# MK12_PIR_LUX.net
KiCad netlist of a schematic drawn in EAGLE
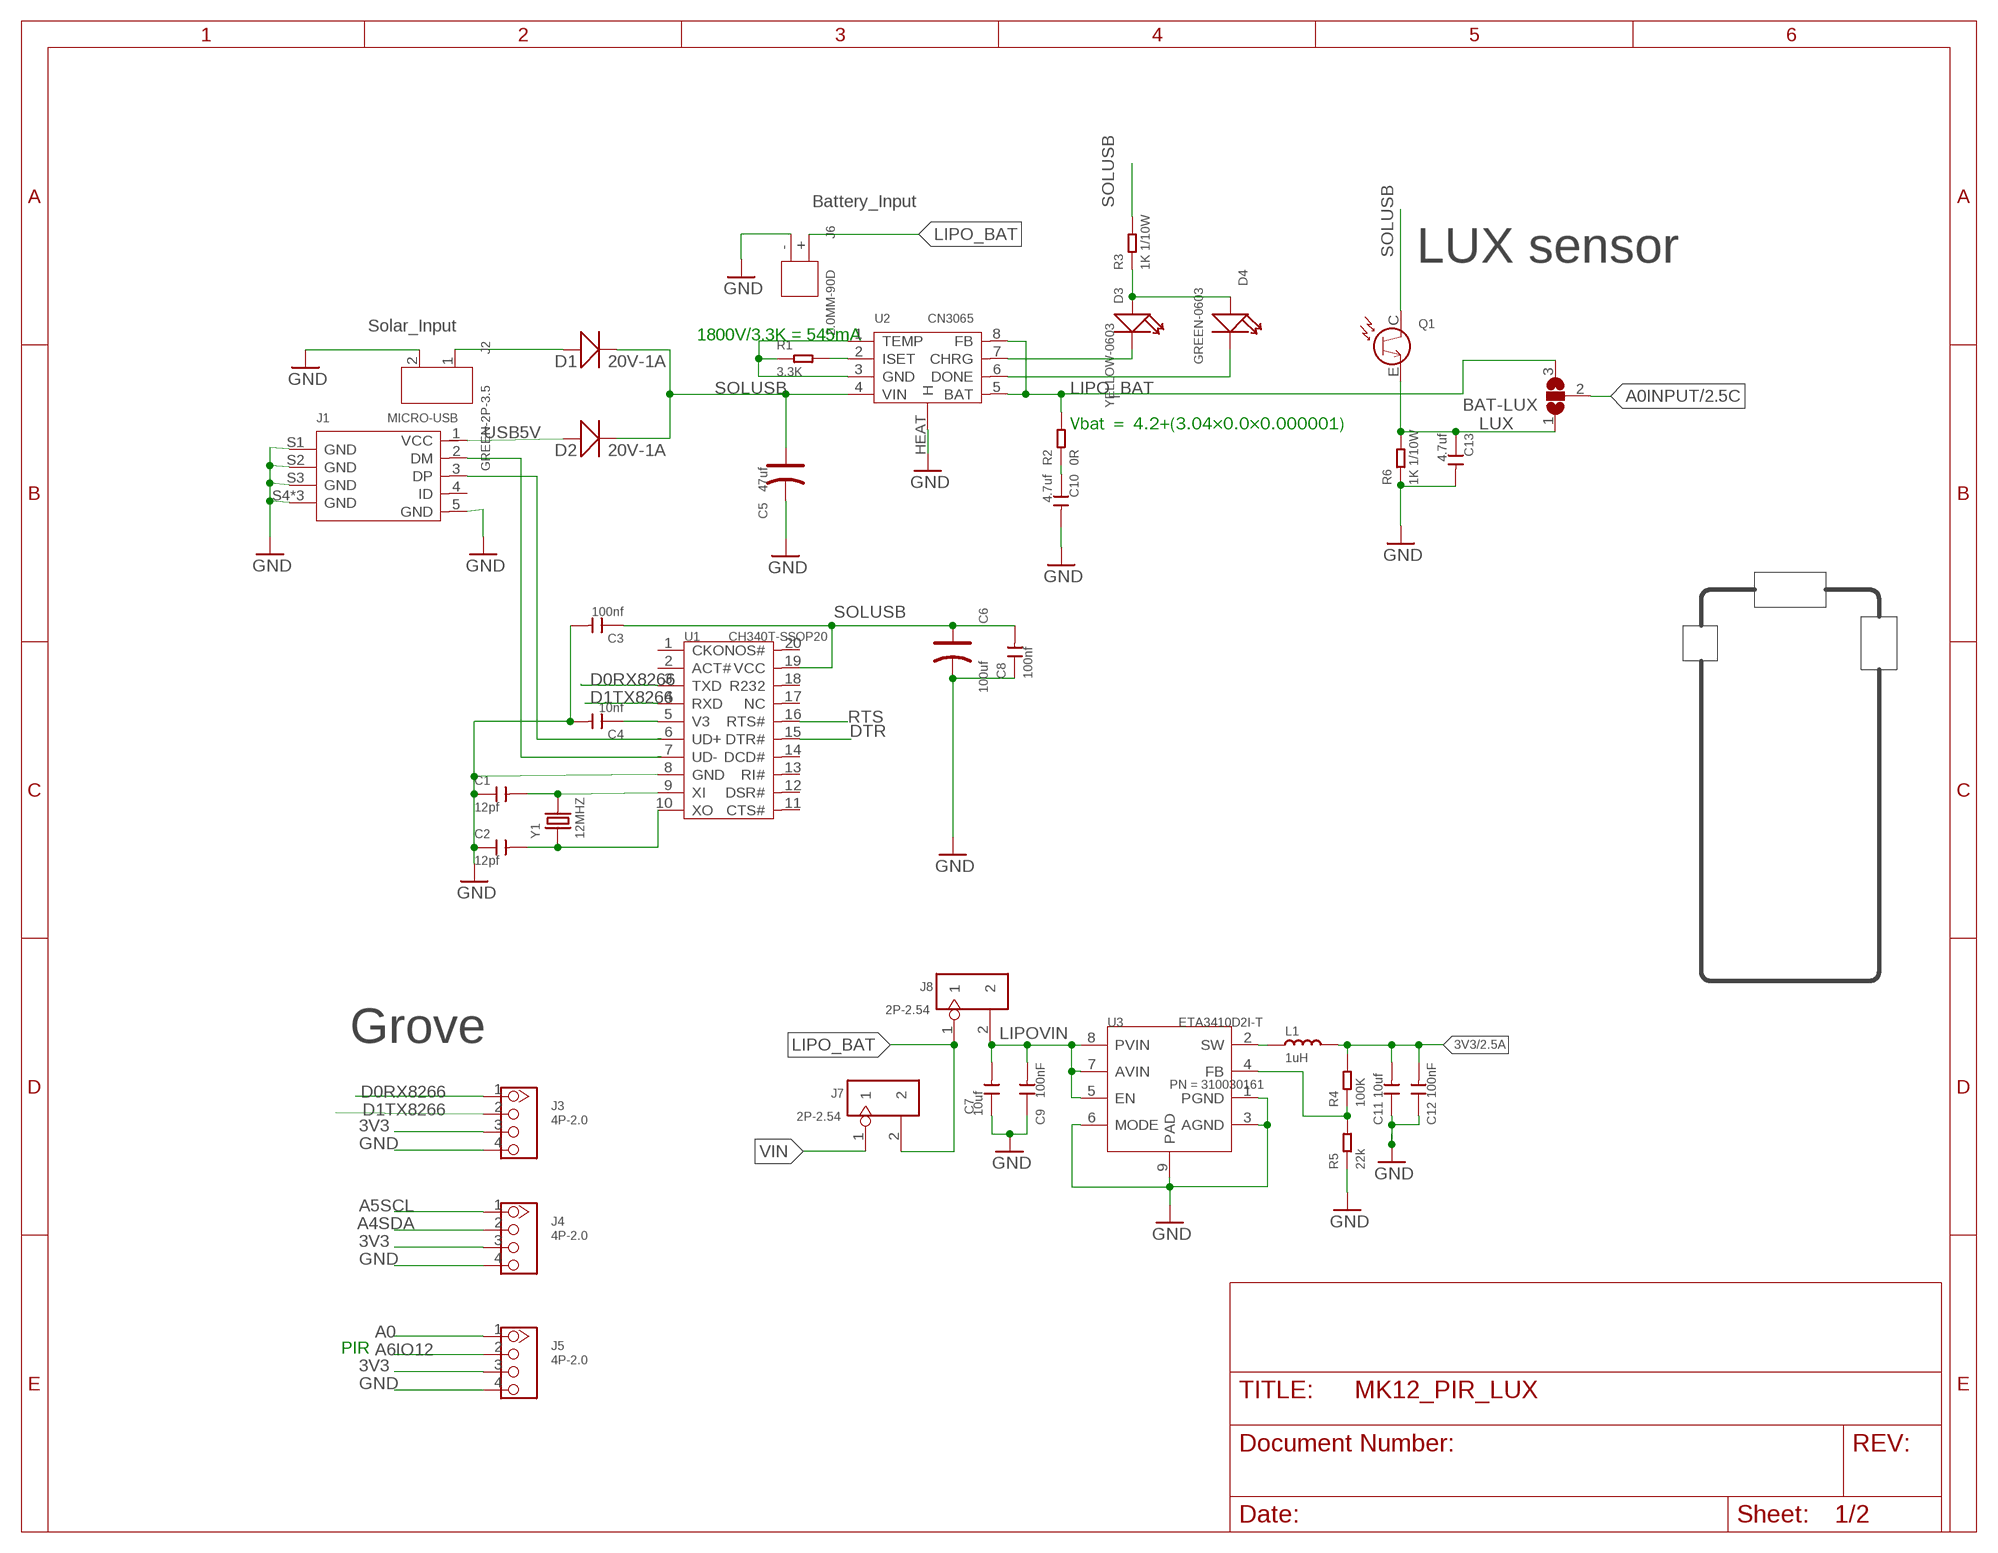
[diagram p0: schematic, sheet 1]
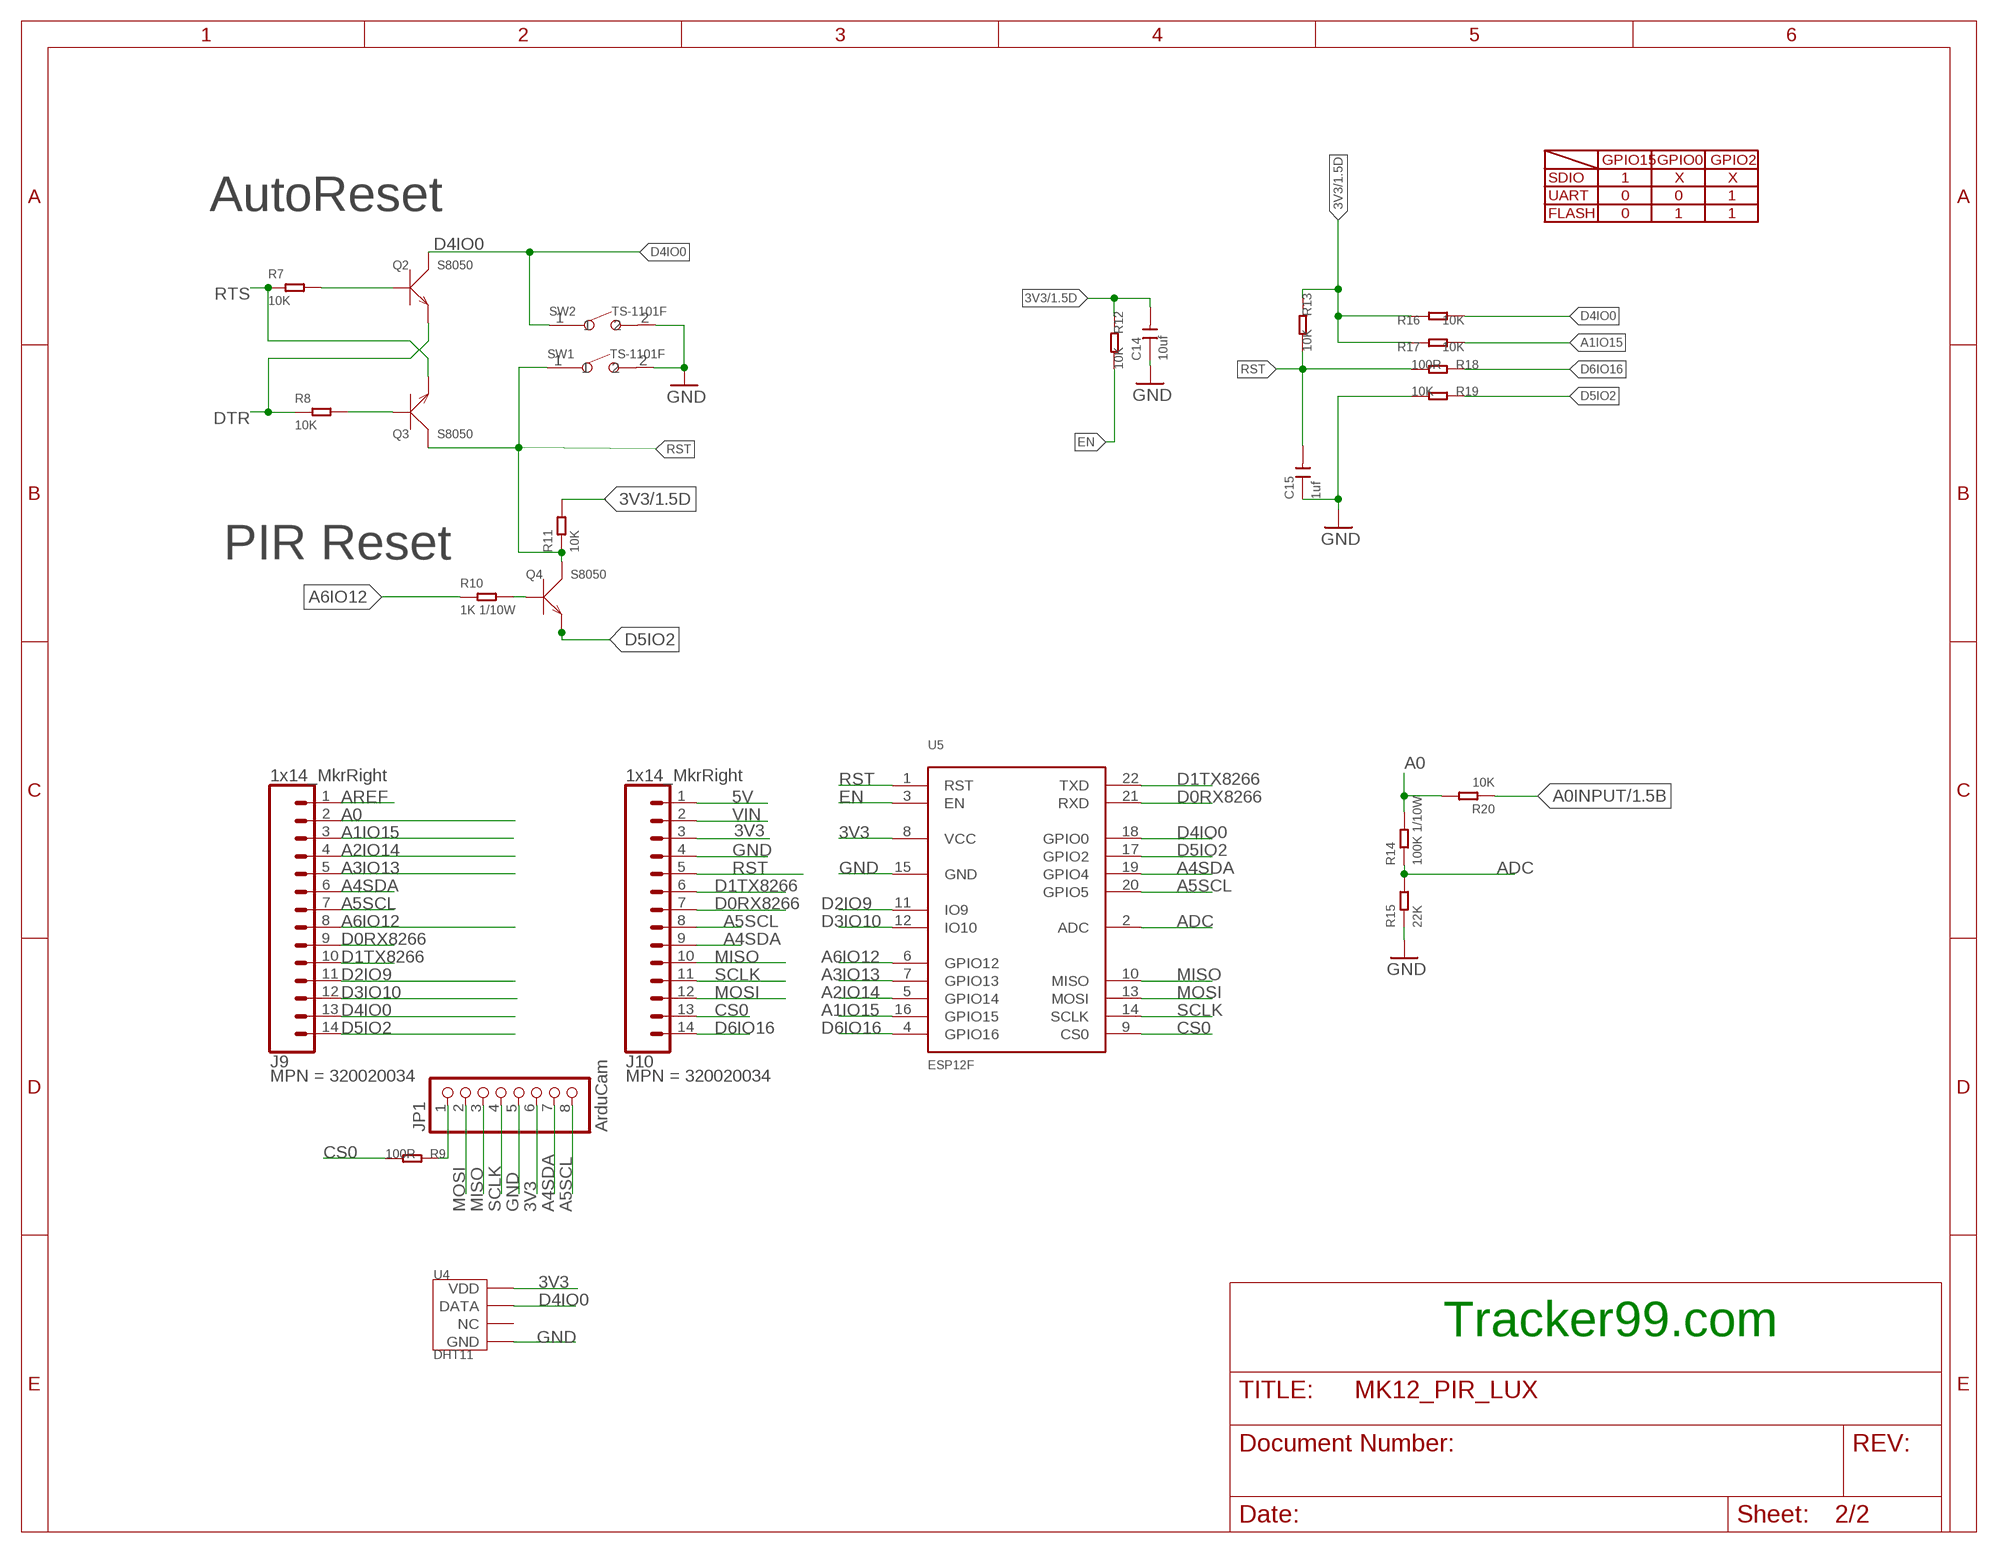
[diagram p1: schematic, sheet 2]

(export (version "E")
  (design (tool "Eeschema 10.0.6"))
  (components
    (comp (ref "BAT-LUX")
      (value "SJ2W")
      (footprint "eagle-import:SJ_2")
      (libsource (lib "eagle-import") (part "SJ2W"))
    )
    (comp (ref "C1")
      (value "12pf")
      (footprint "eagle-import:C0402")
      (fields (field (name "MPN") "CC0402JRNPO9BN120"))
      (libsource (lib "eagle-import") (part "CERAMIC-12PF-50V-5%-NPO(0402)"))
    )
    (comp (ref "C2")
      (value "12pf")
      (footprint "eagle-import:C0402")
      (fields (field (name "MPN") "CC0402JRNPO9BN120"))
      (libsource (lib "eagle-import") (part "CERAMIC-12PF-50V-5%-NPO(0402)"))
    )
    (comp (ref "C3")
      (value "100nf")
      (footprint "eagle-import:C0603")
      (fields (field (name "MPN") "CC0603KRX7R9BB104"))
      (libsource (lib "eagle-import") (part "CERAMIC-100NF-50V-10%-X7R(0603)"))
    )
    (comp (ref "C4")
      (value "10nf")
      (footprint "eagle-import:C0603")
      (fields (field (name "MPN") "CC0603KRX7R9BB103"))
      (libsource (lib "eagle-import") (part "CERAMIC-10NF-50V-10%-X7R(0603)"))
    )
    (comp (ref "C5")
      (value "47uf")
      (footprint "eagle-import:AVX-A")
      (fields (field (name "MPN") "TAJA476*006#NJ"))
      (libsource (lib "eagle-import") (part "TANTALUM-SMD-47UF-6.3V(AVX-A)"))
    )
    (comp (ref "C6")
      (value "100uf")
      (footprint "eagle-import:AVX-B")
      (fields (field (name "MPN") "TAJB107M010#NJ"))
      (libsource (lib "eagle-import") (part "TANTALUM-SMD-100UF-10V(AVX-B)"))
    )
    (comp (ref "C7")
      (value "10uf")
      (footprint "eagle-import:C0805")
      (fields (field (name "MPN") "CC0805KKX5R8BB106"))
      (libsource (lib "eagle-import") (part "CERAMIC-10UF-25V-10%-X5R(0805)"))
    )
    (comp (ref "C8")
      (value "100nf")
      (footprint "eagle-import:C0603")
      (fields (field (name "MPN") "CC0603KRX7R9BB104"))
      (libsource (lib "eagle-import") (part "CERAMIC-100NF-50V-10%-X7R(0603)"))
    )
    (comp (ref "C9")
      (value "100nF")
      (footprint "eagle-import:C0402")
      (libsource (lib "eagle-import") (part "CAP-0402"))
    )
    (comp (ref "C10")
      (value "4.7uf")
      (footprint "eagle-import:C0603")
      (fields (field (name "MPN") "CC0603KRX5R6BB475"))
      (libsource (lib "eagle-import") (part "CERAMIC-4.7UF-10V-10%-X5R(0603)"))
    )
    (comp (ref "C11")
      (value "10uf")
      (footprint "eagle-import:C0805")
      (fields (field (name "MPN") "CC0805KKX5R8BB106"))
      (libsource (lib "eagle-import") (part "CERAMIC-10UF-25V-10%-X5R(0805)"))
    )
    (comp (ref "C12")
      (value "100nF")
      (footprint "eagle-import:C0402")
      (libsource (lib "eagle-import") (part "CAP-0402"))
    )
    (comp (ref "C13")
      (value "4.7uf")
      (footprint "eagle-import:C0603")
      (fields (field (name "MPN") "CC0603KRX5R6BB475"))
      (libsource (lib "eagle-import") (part "CERAMIC-4.7UF-10V-10%-X5R(0603)"))
    )
    (comp (ref "D1")
      (value "20V-1A")
      (footprint "eagle-import:SOD-123")
      (fields (field (name "MPN") "B5819W"))
      (libsource (lib "eagle-import") (part "SMD-DIODE-SCHOTTKY-20V-1A(SOD-123)"))
    )
    (comp (ref "D2")
      (value "20V-1A")
      (footprint "eagle-import:SOD-123")
      (fields (field (name "MPN") "B5819W"))
      (libsource (lib "eagle-import") (part "SMD-DIODE-SCHOTTKY-20V-1A(SOD-123)"))
    )
    (comp (ref "D3")
      (value "YELLOW-0603")
      (footprint "eagle-import:LED-0603")
      (fields (field (name "MPN") "19-217-Y5C-AM1N1VY-3T"))
      (libsource (lib "eagle-import") (part "SMD-LED-CLEAR-YELLOW(0603)"))
    )
    (comp (ref "D4")
      (value "GREEN-0603")
      (footprint "eagle-import:LED-0603")
      (fields (field (name "MPN") "19-217-G7C-AN1P2-3T"))
      (libsource (lib "eagle-import") (part "SMD-LED-CLEAR-GREEN(0603)"))
    )
    (comp (ref "J1")
      (value "MICRO-USB")
      (footprint "eagle-import:MICRO-USB5+4P-SMD-0.65-B")
      (fields (field (name "EAGLEUP") "USB-MICROB;2.54mm"))
      (libsource (lib "eagle-import") (part "MICRO-USB5+4P'5+4P'"))
    )
    (comp (ref "J2")
      (value "GREEN-2P-3.5")
      (footprint "eagle-import:H2-3.5-7.0X7.0MM")
      (libsource (lib "eagle-import") (part "SCREW-TERMINAL-GREEN(2P-3.5)"))
    )
    (comp (ref "J3")
      (value "4P-2.0")
      (footprint "eagle-import:HW4-2.0")
      (libsource (lib "eagle-import") (part "GROVE-CONNECTOR-DIP(4P-2.0)"))
    )
    (comp (ref "J4")
      (value "4P-2.0")
      (footprint "eagle-import:HW4-2.0")
      (libsource (lib "eagle-import") (part "GROVE-CONNECTOR-DIP(4P-2.0)"))
    )
    (comp (ref "J5")
      (value "4P-2.0")
      (footprint "eagle-import:HW4-2.0")
      (libsource (lib "eagle-import") (part "GROVE-CONNECTOR-DIP(4P-2.0)"))
    )
    (comp (ref "J6")
      (value "2.0MM-90D")
      (footprint "eagle-import:H2-2.0-90D")
      (libsource (lib "eagle-import") (part "CONN-HEADER-PH-SIDE-(2P-2.0MM)'90D'"))
    )
    (comp (ref "J7")
      (value "2P-2.54")
      (footprint "eagle-import:H2-2.54")
      (fields (field (name "MPN") "P125-1102A0BS116A3"))
      (libsource (lib "eagle-import") (part "DIP-WHITE-MALE-HEADER-VERT(2P-2.54)"))
    )
    (comp (ref "J8")
      (value "2P-2.54")
      (footprint "eagle-import:H2-2.54")
      (fields (field (name "MPN") "P125-1102A0BS116A3"))
      (libsource (lib "eagle-import") (part "DIP-WHITE-MALE-HEADER-VERT(2P-2.54)"))
    )
    (comp (ref "L1")
      (value "1uH")
      (footprint "eagle-import:L0603")
      (libsource (lib "eagle-import") (part "INDUCTOR/FERRITE-BEAD'0603'"))
    )
    (comp (ref "Q1")
      (value "EAALST05RDMA0")
      (footprint "eagle-import:EAALST05RDMA0")
      (libsource (lib "eagle-import") (part "EAALST05RDMA0"))
    )
    (comp (ref "R1")
      (value "3.3K")
      (footprint "eagle-import:R0603")
      (libsource (lib "eagle-import") (part "SMD-RES-3.3K-5%-1/10W(0603)"))
    )
    (comp (ref "R2")
      (value "0R")
      (footprint "eagle-import:R0603")
      (fields (field (name "MPN") "RC0603JR-070RL"))
      (libsource (lib "eagle-import") (part "SMD-RES-0R-5%-1/10W(0603)"))
    )
    (comp (ref "R3")
      (value "1K 1/10W")
      (footprint "eagle-import:R0603")
      (fields (field (name "MPN") "RC0603JR-071KL"))
      (libsource (lib "eagle-import") (part "SMD-RES-1K-5%-1/10W(0603)"))
    )
    (comp (ref "R4")
      (value "100K")
      (footprint "eagle-import:R0402")
      (fields (field (name "MPN") "RC0402FR-07100KL"))
      (libsource (lib "eagle-import") (part "SMD-RES-100K-1%-1/16W(0402)"))
    )
    (comp (ref "R5")
      (value "22k")
      (footprint "eagle-import:R0402")
      (fields (field (name "MPN") "RC0402FR-0722KL"))
      (libsource (lib "eagle-import") (part "SMD-RES-22K-1%-1/16W(0402)"))
    )
    (comp (ref "R6")
      (value "1K 1/10W")
      (footprint "eagle-import:R0603")
      (fields (field (name "MPN") "RC0603JR-071KL"))
      (libsource (lib "eagle-import") (part "SMD-RES-1K-5%-1/10W(0603)"))
    )
    (comp (ref "U1")
      (value "CH340T-SSOP20")
      (footprint "eagle-import:SSOP20-0.65-7.6X5.2MM")
      (fields (field (name "MPN") "CH340T"))
      (libsource (lib "eagle-import") (part "INTERFACE-CH340T(SSOP20)"))
    )
    (comp (ref "U2")
      (value "CN3065")
      (footprint "eagle-import:DFN-8")
      (libsource (lib "eagle-import") (part "PMIC-CN3065-DFN8"))
    )
    (comp (ref "U3")
      (value "ETA3410D2I-T")
      (footprint "eagle-import:DFN8G-0.5-2X2MM")
      (fields (field (name "PN") "310030161"))
      (libsource (lib "eagle-import") (part "CONVERTER-ETA3410"))
    )
    (comp (ref "Y1")
      (value "12MHZ")
      (footprint "eagle-import:X2-SMD-5.0X3.2X1.3MM")
      (fields (field (name "MPN") "5032/2P"))
      (libsource (lib "eagle-import") (part "SMD-CRYSTAL-12MHZ-20PF-20PPM-40R(2P-5.0X3.2MM)"))
    )
    (comp (ref "C14")
      (value "10uf")
      (footprint "eagle-import:C0603")
      (fields (field (name "MPN") "CC0603KRX5R6BB106"))
      (libsource (lib "eagle-import") (part "CERAMIC-10UF-10V-10%-X5R(0603)"))
    )
    (comp (ref "C15")
      (value "1uf")
      (footprint "eagle-import:C0603")
      (fields (field (name "MPN") "CC0603KRX7R8BB105"))
      (libsource (lib "eagle-import") (part "CERAMIC-1UF-25V-10%-X7R(0603)"))
    )
    (comp (ref "J9")
      (value "1x14_MkrRight")
      (footprint "eagle-import:1X14_LOCK")
      (fields (field (name "MPN") "320020034"))
      (libsource (lib "eagle-import") (part "CONN_14LOCK"))
    )
    (comp (ref "J10")
      (value "1x14_MkrRight")
      (footprint "eagle-import:1X14_LOCK")
      (fields (field (name "MPN") "320020034"))
      (libsource (lib "eagle-import") (part "CONN_14LOCK"))
    )
    (comp (ref "JP1")
      (value "ArduCam")
      (footprint "eagle-import:MILLER_1X08-LOCK")
      (libsource (lib "eagle-import") (part "MILLER_PINHD-1X8LOCK"))
    )
    (comp (ref "Q2")
      (value "S8050")
      (footprint "eagle-import:SOT-23")
      (libsource (lib "eagle-import") (part "SMD-TRANSISTORS-NPN-25V-500MW-S8050(SOT-23)"))
    )
    (comp (ref "Q3")
      (value "S8050")
      (footprint "eagle-import:SOT-23")
      (libsource (lib "eagle-import") (part "SMD-TRANSISTORS-NPN-25V-500MW-S8050(SOT-23)"))
    )
    (comp (ref "Q4")
      (value "S8050")
      (footprint "eagle-import:SOT-23")
      (libsource (lib "eagle-import") (part "SMD-TRANSISTORS-NPN-25V-500MW-S8050(SOT-23)"))
    )
    (comp (ref "R7")
      (value "10K")
      (footprint "eagle-import:R0402")
      (fields (field (name "MPN") "RC0402JR-0710KL"))
      (libsource (lib "eagle-import") (part "SMD-RES-10K-5%-1/(0402)"))
    )
    (comp (ref "R8")
      (value "10K")
      (footprint "eagle-import:R0402")
      (fields (field (name "MPN") "RC0402JR-0710KL"))
      (libsource (lib "eagle-import") (part "SMD-RES-10K-5%-1/(0402)"))
    )
    (comp (ref "R9")
      (value "100R")
      (footprint "eagle-import:R0603")
      (fields (field (name "MPN") "RC0603JR-07100RL"))
      (libsource (lib "eagle-import") (part "SMD-RES-100R-5%-1/10W(0603)"))
    )
    (comp (ref "R10")
      (value "1K 1/10W")
      (footprint "eagle-import:R0603")
      (fields (field (name "MPN") "RC0603JR-071KL"))
      (libsource (lib "eagle-import") (part "SMD-RES-1K-5%-1/10W(0603)"))
    )
    (comp (ref "R11")
      (value "10K")
      (footprint "eagle-import:R0402")
      (fields (field (name "MPN") "RC0402JR-0710KL"))
      (libsource (lib "eagle-import") (part "SMD-RES-10K-5%-1/(0402)"))
    )
    (comp (ref "R12")
      (value "10K")
      (footprint "eagle-import:SEEED-RESISTOR_R0402")
      (fields (field (name "MPN") "RC0402JR-0710KL"))
      (libsource (lib "eagle-import") (part "SEEED-RESISTOR_SMD-RES-10K-5%-1/(0402)"))
    )
    (comp (ref "R13")
      (value "10K")
      (footprint "eagle-import:SEEED-RESISTOR_R0402")
      (fields (field (name "MPN") "RC0402JR-0710KL"))
      (libsource (lib "eagle-import") (part "SEEED-RESISTOR_SMD-RES-10K-5%-1/(0402)"))
    )
    (comp (ref "R14")
      (value "100K 1/10W")
      (footprint "eagle-import:R0603")
      (fields (field (name "MPN") "RC0603JR-07100KL"))
      (libsource (lib "eagle-import") (part "SMD-RES-100K-5%-1/10W(0603)"))
    )
    (comp (ref "R15")
      (value "22K")
      (footprint "eagle-import:R0603")
      (fields (field (name "MPN") "RC0603JR-0722KL"))
      (libsource (lib "eagle-import") (part "SMD-RES-22K-5%-1/10W(0603)"))
    )
    (comp (ref "R16")
      (value "10K")
      (footprint "eagle-import:SEEED-RESISTOR_R0402")
      (fields (field (name "MPN") "RC0402JR-0710KL"))
      (libsource (lib "eagle-import") (part "SEEED-RESISTOR_SMD-RES-10K-5%-1/(0402)"))
    )
    (comp (ref "R17")
      (value "10K")
      (footprint "eagle-import:SEEED-RESISTOR_R0402")
      (fields (field (name "MPN") "RC0402JR-0710KL"))
      (libsource (lib "eagle-import") (part "SEEED-RESISTOR_SMD-RES-10K-5%-1/(0402)"))
    )
    (comp (ref "R18")
      (value "100R")
      (footprint "eagle-import:R0603")
      (fields (field (name "MPN") "RC0603JR-07100RL"))
      (libsource (lib "eagle-import") (part "SMD-RES-100R-5%-1/10W(0603)"))
    )
    (comp (ref "R19")
      (value "10K")
      (footprint "eagle-import:SEEED-RESISTOR_R0402")
      (fields (field (name "MPN") "RC0402JR-0710KL"))
      (libsource (lib "eagle-import") (part "SEEED-RESISTOR_SMD-RES-10K-5%-1/(0402)"))
    )
    (comp (ref "R20")
      (value "10K")
      (footprint "eagle-import:R0402")
      (fields (field (name "MPN") "RC0402JR-0710KL"))
      (libsource (lib "eagle-import") (part "SMD-RES-10K-5%-1/(0402)"))
    )
    (comp (ref "SW1")
      (value "TS-1101F")
      (footprint "eagle-import:SW2-5.0-6.0X3.0X4.3MM")
      (libsource (lib "eagle-import") (part "DIP-BUTTON(2P-6.0X3.0X4.3MM)-TS-1101F"))
    )
    (comp (ref "SW2")
      (value "TS-1101F")
      (footprint "eagle-import:SW2-5.0-6.0X3.0X4.3MM")
      (libsource (lib "eagle-import") (part "DIP-BUTTON(2P-6.0X3.0X4.3MM)-TS-1101F"))
    )
    (comp (ref "U4")
      (value "DHT11")
      (footprint "eagle-import:SNR4-2.54-15.5X12.0X5.5MM")
      (libsource (lib "eagle-import") (part "TEM-HUM-DHT11(4P-15.5X12.0MM)"))
    )
    (comp (ref "U5")
      (value "ESP12F")
      (footprint "eagle-import:ESP-12F")
      (libsource (lib "eagle-import") (part "ESP-12F"))
    )
  )
  (nets
    (net (code "1") (name "3V3") (class "Default")
      (node (ref "C11") (pin "2") (pinfunction "2_2") (pintype "passive"))
      (node (ref "C12") (pin "2") (pinfunction "2_2") (pintype "passive"))
      (node (ref "C14") (pin "2") (pinfunction "2_2") (pintype "passive"))
      (node (ref "J10") (pin "3") (pinfunction "3_3") (pintype "passive"))
      (node (ref "J3") (pin "3") (pinfunction "3_3") (pintype "bidirectional"))
      (node (ref "J4") (pin "3") (pinfunction "3_3") (pintype "bidirectional"))
      (node (ref "J5") (pin "3") (pinfunction "3_3") (pintype "bidirectional"))
      (node (ref "JP1") (pin "6") (pinfunction "6_6") (pintype "passive"))
      (node (ref "L1") (pin "2") (pinfunction "2_2") (pintype "passive"))
      (node (ref "R11") (pin "2") (pinfunction "2_2") (pintype "passive"))
      (node (ref "R12") (pin "1") (pinfunction "1_1") (pintype "passive"))
      (node (ref "R13") (pin "1") (pinfunction "1_1") (pintype "passive"))
      (node (ref "R16") (pin "1") (pinfunction "1_1") (pintype "passive"))
      (node (ref "R17") (pin "1") (pinfunction "1_1") (pintype "passive"))
      (node (ref "R4") (pin "2") (pinfunction "2_2") (pintype "passive"))
      (node (ref "U4") (pin "1") (pinfunction "VDD_1") (pintype "power_in"))
      (node (ref "U5") (pin "8") (pinfunction "VCC_8") (pintype "bidirectional"))
    )
    (net (code "2") (name "5V") (class "Default")
      (node (ref "J10") (pin "1") (pinfunction "1_1") (pintype "passive"))
    )
    (net (code "3") (name "A0") (class "Default")
      (node (ref "J5") (pin "1") (pinfunction "1_1") (pintype "bidirectional"))
      (node (ref "J9") (pin "2") (pinfunction "2_2") (pintype "passive"))
      (node (ref "R14") (pin "2") (pinfunction "2_2") (pintype "passive"))
      (node (ref "R20") (pin "2") (pinfunction "2_2") (pintype "passive"))
    )
    (net (code "4") (name "A0INPUT") (class "Default")
      (node (ref "BAT-LUX") (pin "2") (pinfunction "2_2") (pintype "passive"))
      (node (ref "R20") (pin "1") (pinfunction "1_1") (pintype "passive"))
    )
    (net (code "5") (name "A1IO15") (class "Default")
      (node (ref "J9") (pin "3") (pinfunction "3_3") (pintype "passive"))
      (node (ref "R17") (pin "2") (pinfunction "2_2") (pintype "passive"))
      (node (ref "U5") (pin "16") (pinfunction "GPIO15_16") (pintype "bidirectional"))
    )
    (net (code "6") (name "A2IO14") (class "Default")
      (node (ref "J9") (pin "4") (pinfunction "4_4") (pintype "passive"))
      (node (ref "U5") (pin "5") (pinfunction "GPIO14_5") (pintype "bidirectional"))
    )
    (net (code "7") (name "A3IO13") (class "Default")
      (node (ref "J9") (pin "5") (pinfunction "5_5") (pintype "passive"))
      (node (ref "U5") (pin "7") (pinfunction "GPIO13_7") (pintype "bidirectional"))
    )
    (net (code "8") (name "A4SDA") (class "Default")
      (node (ref "J10") (pin "9") (pinfunction "9_9") (pintype "passive"))
      (node (ref "J4") (pin "2") (pinfunction "2_2") (pintype "bidirectional"))
      (node (ref "J9") (pin "6") (pinfunction "6_6") (pintype "passive"))
      (node (ref "JP1") (pin "7") (pinfunction "7_7") (pintype "passive"))
      (node (ref "U5") (pin "19") (pinfunction "GPIO4_19") (pintype "bidirectional"))
    )
    (net (code "9") (name "A5SCL") (class "Default")
      (node (ref "J10") (pin "8") (pinfunction "8_8") (pintype "passive"))
      (node (ref "J4") (pin "1") (pinfunction "1_1") (pintype "bidirectional"))
      (node (ref "J9") (pin "7") (pinfunction "7_7") (pintype "passive"))
      (node (ref "JP1") (pin "8") (pinfunction "8_8") (pintype "passive"))
      (node (ref "U5") (pin "20") (pinfunction "GPIO5_20") (pintype "bidirectional"))
    )
    (net (code "10") (name "A6IO12") (class "Default")
      (node (ref "J5") (pin "2") (pinfunction "2_2") (pintype "bidirectional"))
      (node (ref "J9") (pin "8") (pinfunction "8_8") (pintype "passive"))
      (node (ref "R10") (pin "1") (pinfunction "1_1") (pintype "passive"))
      (node (ref "U5") (pin "6") (pinfunction "GPIO12_6") (pintype "bidirectional"))
    )
    (net (code "11") (name "ADC") (class "Default")
      (node (ref "R14") (pin "1") (pinfunction "1_1") (pintype "passive"))
      (node (ref "R15") (pin "2") (pinfunction "2_2") (pintype "passive"))
      (node (ref "U5") (pin "2") (pinfunction "ADC_2") (pintype "bidirectional"))
    )
    (net (code "12") (name "AREF") (class "Default")
      (node (ref "J9") (pin "1") (pinfunction "1_1") (pintype "passive"))
    )
    (net (code "13") (name "CS0") (class "Default")
      (node (ref "J10") (pin "13") (pinfunction "13_13") (pintype "passive"))
      (node (ref "R9") (pin "2") (pinfunction "2_2") (pintype "passive"))
      (node (ref "U5") (pin "9") (pinfunction "CS0_9") (pintype "bidirectional"))
    )
    (net (code "14") (name "D0RX8266") (class "Default")
      (node (ref "J10") (pin "7") (pinfunction "7_7") (pintype "passive"))
      (node (ref "J3") (pin "1") (pinfunction "1_1") (pintype "bidirectional"))
      (node (ref "J9") (pin "9") (pinfunction "9_9") (pintype "passive"))
      (node (ref "U1") (pin "3") (pinfunction "TXD_3") (pintype "output"))
      (node (ref "U5") (pin "21") (pinfunction "RXD_21") (pintype "bidirectional"))
    )
    (net (code "15") (name "D1TX8266") (class "Default")
      (node (ref "J10") (pin "6") (pinfunction "6_6") (pintype "passive"))
      (node (ref "J3") (pin "2") (pinfunction "2_2") (pintype "bidirectional"))
      (node (ref "J9") (pin "10") (pinfunction "10_10") (pintype "passive"))
      (node (ref "U1") (pin "4") (pinfunction "RXD_4") (pintype "input"))
      (node (ref "U5") (pin "22") (pinfunction "TXD_22") (pintype "bidirectional"))
    )
    (net (code "16") (name "D2IO9") (class "Default")
      (node (ref "J9") (pin "11") (pinfunction "11_11") (pintype "passive"))
      (node (ref "U5") (pin "11") (pinfunction "IO9_11") (pintype "bidirectional"))
    )
    (net (code "17") (name "D3IO10") (class "Default")
      (node (ref "J9") (pin "12") (pinfunction "12_12") (pintype "passive"))
      (node (ref "U5") (pin "12") (pinfunction "IO10_12") (pintype "bidirectional"))
    )
    (net (code "18") (name "D4IO0") (class "Default")
      (node (ref "J9") (pin "13") (pinfunction "13_13") (pintype "passive"))
      (node (ref "Q2") (pin "3") (pinfunction "C_3") (pintype "passive"))
      (node (ref "R16") (pin "2") (pinfunction "2_2") (pintype "passive"))
      (node (ref "SW2") (pin "1") (pinfunction "1_1") (pintype "bidirectional"))
      (node (ref "U4") (pin "2") (pinfunction "DATA_2") (pintype "bidirectional"))
      (node (ref "U5") (pin "18") (pinfunction "GPIO0_18") (pintype "bidirectional"))
    )
    (net (code "19") (name "D5IO2") (class "Default")
      (node (ref "J9") (pin "14") (pinfunction "14_14") (pintype "passive"))
      (node (ref "Q4") (pin "2") (pinfunction "E_2") (pintype "passive"))
      (node (ref "R19") (pin "1") (pinfunction "1_1") (pintype "passive"))
      (node (ref "U5") (pin "17") (pinfunction "GPIO2_17") (pintype "bidirectional"))
    )
    (net (code "20") (name "D6IO16") (class "Default")
      (node (ref "J10") (pin "14") (pinfunction "14_14") (pintype "passive"))
      (node (ref "R18") (pin "1") (pinfunction "1_1") (pintype "passive"))
      (node (ref "U5") (pin "4") (pinfunction "GPIO16_4") (pintype "bidirectional"))
    )
    (net (code "21") (name "DTR") (class "Default")
      (node (ref "Q2") (pin "2") (pinfunction "E_2") (pintype "passive"))
      (node (ref "R8") (pin "1") (pinfunction "1_1") (pintype "passive"))
      (node (ref "U1") (pin "15") (pinfunction "DTR#_15") (pintype "output"))
    )
    (net (code "22") (name "EN") (class "Default")
      (node (ref "R12") (pin "2") (pinfunction "2_2") (pintype "passive"))
      (node (ref "U5") (pin "3") (pinfunction "EN_3") (pintype "bidirectional"))
    )
    (net (code "23") (name "GND") (class "Default")
      (node (ref "C1") (pin "1") (pinfunction "1_1") (pintype "passive"))
      (node (ref "C10") (pin "2") (pinfunction "2_2") (pintype "passive"))
      (node (ref "C11") (pin "1") (pinfunction "1_1") (pintype "passive"))
      (node (ref "C12") (pin "1") (pinfunction "1_1") (pintype "passive"))
      (node (ref "C13") (pin "2") (pinfunction "2_2") (pintype "passive"))
      (node (ref "C14") (pin "1") (pinfunction "1_1") (pintype "passive"))
      (node (ref "C15") (pin "1") (pinfunction "1_1") (pintype "passive"))
      (node (ref "C2") (pin "1") (pinfunction "1_1") (pintype "passive"))
      (node (ref "C3") (pin "2") (pinfunction "2_2") (pintype "passive"))
      (node (ref "C4") (pin "2") (pinfunction "2_2") (pintype "passive"))
      (node (ref "C5") (pin "-") (pinfunction "-_-") (pintype "passive"))
      (node (ref "C6") (pin "-") (pinfunction "-_-") (pintype "passive"))
      (node (ref "C7") (pin "1") (pinfunction "1_1") (pintype "passive"))
      (node (ref "C8") (pin "1") (pinfunction "1_1") (pintype "passive"))
      (node (ref "C9") (pin "1") (pinfunction "1_1") (pintype "passive"))
      (node (ref "J1") (pin "5") (pinfunction "GND_5") (pintype "bidirectional"))
      (node (ref "J1") (pin "S1") (pinfunction "GND_S1") (pintype "bidirectional"))
      (node (ref "J1") (pin "S2") (pinfunction "GND_S2") (pintype "bidirectional"))
      (node (ref "J1") (pin "S3") (pinfunction "GND_S3") (pintype "bidirectional"))
      (node (ref "J1") (pin "S4") (pinfunction "GND_S4") (pintype "bidirectional"))
      (node (ref "J1") (pin "S5") (pinfunction "GND_S5") (pintype "bidirectional"))
      (node (ref "J1") (pin "S6") (pinfunction "GND_S6") (pintype "bidirectional"))
      (node (ref "J10") (pin "4") (pinfunction "4_4") (pintype "passive"))
      (node (ref "J2") (pin "2") (pinfunction "2_2") (pintype "bidirectional"))
      (node (ref "J3") (pin "4") (pinfunction "4_4") (pintype "bidirectional"))
      (node (ref "J4") (pin "4") (pinfunction "4_4") (pintype "bidirectional"))
      (node (ref "J5") (pin "4") (pinfunction "4_4") (pintype "bidirectional"))
      (node (ref "J6") (pin "-") (pinfunction "P$2_-") (pintype "bidirectional"))
      (node (ref "JP1") (pin "5") (pinfunction "5_5") (pintype "passive"))
      (node (ref "R1") (pin "1") (pinfunction "1_1") (pintype "passive"))
      (node (ref "R15") (pin "1") (pinfunction "1_1") (pintype "passive"))
      (node (ref "R19") (pin "2") (pinfunction "2_2") (pintype "passive"))
      (node (ref "R5") (pin "1") (pinfunction "1_1") (pintype "passive"))
      (node (ref "R6") (pin "1") (pinfunction "1_1") (pintype "passive"))
      (node (ref "SW1") (pin "2") (pinfunction "2_2") (pintype "bidirectional"))
      (node (ref "SW2") (pin "2") (pinfunction "2_2") (pintype "bidirectional"))
      (node (ref "U1") (pin "8") (pinfunction "GND_8") (pintype "power_in"))
      (node (ref "U2") (pin "1") (pinfunction "TEMP_1") (pintype "input"))
      (node (ref "U2") (pin "3") (pinfunction "GND_3") (pintype "power_in"))
      (node (ref "U2") (pin "HEAT") (pinfunction "H_HEAT") (pintype "bidirectional"))
      (node (ref "U3") (pin "1") (pinfunction "PGND_1") (pintype "bidirectional"))
      (node (ref "U3") (pin "3") (pinfunction "AGND_3") (pintype "bidirectional"))
      (node (ref "U3") (pin "6") (pinfunction "MODE_6") (pintype "bidirectional"))
      (node (ref "U3") (pin "9") (pinfunction "PAD_9") (pintype "bidirectional"))
      (node (ref "U4") (pin "4") (pinfunction "GND_4") (pintype "power_in"))
      (node (ref "U5") (pin "15") (pinfunction "GND_15") (pintype "bidirectional"))
    )
    (net (code "24") (name "LIPOVIN") (class "Default")
      (node (ref "C7") (pin "2") (pinfunction "2_2") (pintype "passive"))
      (node (ref "C9") (pin "2") (pinfunction "2_2") (pintype "passive"))
      (node (ref "J8") (pin "2") (pinfunction "2_2") (pintype "bidirectional"))
      (node (ref "U3") (pin "5") (pinfunction "EN_5") (pintype "bidirectional"))
      (node (ref "U3") (pin "7") (pinfunction "AVIN_7") (pintype "bidirectional"))
      (node (ref "U3") (pin "8") (pinfunction "PVIN_8") (pintype "bidirectional"))
    )
    (net (code "25") (name "LIPO_BAT") (class "Default")
      (node (ref "BAT-LUX") (pin "3") (pinfunction "3_3") (pintype "passive"))
      (node (ref "J6") (pin "+") (pinfunction "P$1_+") (pintype "bidirectional"))
      (node (ref "J7") (pin "2") (pinfunction "2_2") (pintype "bidirectional"))
      (node (ref "J8") (pin "1") (pinfunction "1_1") (pintype "bidirectional"))
      (node (ref "R2") (pin "2") (pinfunction "2_2") (pintype "passive"))
      (node (ref "U2") (pin "5") (pinfunction "BAT_5") (pintype "bidirectional"))
      (node (ref "U2") (pin "8") (pinfunction "FB_8") (pintype "input"))
    )
    (net (code "26") (name "LUX") (class "Default")
      (node (ref "BAT-LUX") (pin "1") (pinfunction "1_1") (pintype "passive"))
      (node (ref "C13") (pin "1") (pinfunction "1_1") (pintype "passive"))
      (node (ref "Q1") (pin "E") (pinfunction "E_E") (pintype "bidirectional"))
      (node (ref "R6") (pin "2") (pinfunction "2_2") (pintype "passive"))
    )
    (net (code "27") (name "MISO") (class "Default")
      (node (ref "J10") (pin "10") (pinfunction "10_10") (pintype "passive"))
      (node (ref "JP1") (pin "3") (pinfunction "3_3") (pintype "passive"))
      (node (ref "U5") (pin "10") (pinfunction "MISO_10") (pintype "bidirectional"))
    )
    (net (code "28") (name "MOSI") (class "Default")
      (node (ref "J10") (pin "12") (pinfunction "12_12") (pintype "passive"))
      (node (ref "JP1") (pin "2") (pinfunction "2_2") (pintype "passive"))
      (node (ref "U5") (pin "13") (pinfunction "MOSI_13") (pintype "bidirectional"))
    )
    (net (code "29") (name "NOS#") (class "Default")
      (node (ref "U1") (pin "20") (pinfunction "NOS#_20") (pintype "power_in"))
    )
    (net (code "30") (name "Net-(C10-Pad1)") (class "Default")
      (node (ref "C10") (pin "1") (pinfunction "1_1") (pintype "passive"))
      (node (ref "R2") (pin "1") (pinfunction "1_1") (pintype "passive"))
    )
    (net (code "31") (name "Net-(D1-Pad+)") (class "Default")
      (node (ref "D1") (pin "+") (pinfunction "+_+") (pintype "passive"))
      (node (ref "J2") (pin "1") (pinfunction "1_1") (pintype "bidirectional"))
    )
    (net (code "32") (name "Net-(D3-Pad+)") (class "Default")
      (node (ref "D3") (pin "+") (pinfunction "+_+") (pintype "passive"))
      (node (ref "D4") (pin "+") (pinfunction "+_+") (pintype "passive"))
      (node (ref "R3") (pin "1") (pinfunction "1_1") (pintype "passive"))
    )
    (net (code "33") (name "Net-(J1-DM)") (class "Default")
      (node (ref "J1") (pin "2") (pinfunction "DM_2") (pintype "bidirectional"))
      (node (ref "U1") (pin "7") (pinfunction "UD-_7") (pintype "bidirectional"))
    )
    (net (code "34") (name "Net-(J1-DP)") (class "Default")
      (node (ref "J1") (pin "3") (pinfunction "DP_3") (pintype "bidirectional"))
      (node (ref "U1") (pin "6") (pinfunction "UD+_6") (pintype "bidirectional"))
    )
    (net (code "35") (name "Net-(JP1-Pad1)") (class "Default")
      (node (ref "JP1") (pin "1") (pinfunction "1_1") (pintype "passive"))
      (node (ref "R9") (pin "1") (pinfunction "1_1") (pintype "passive"))
    )
    (net (code "36") (name "Net-(Q2-B)") (class "Default")
      (node (ref "Q2") (pin "1") (pinfunction "B_1") (pintype "passive"))
      (node (ref "R7") (pin "2") (pinfunction "2_2") (pintype "passive"))
    )
    (net (code "37") (name "Net-(Q3-B)") (class "Default")
      (node (ref "Q3") (pin "1") (pinfunction "B_1") (pintype "passive"))
      (node (ref "R8") (pin "2") (pinfunction "2_2") (pintype "passive"))
    )
    (net (code "38") (name "Net-(Q4-B)") (class "Default")
      (node (ref "Q4") (pin "1") (pinfunction "B_1") (pintype "passive"))
      (node (ref "R10") (pin "2") (pinfunction "2_2") (pintype "passive"))
    )
    (net (code "39") (name "Net-(Q4-C)") (class "Default")
      (node (ref "Q4") (pin "3") (pinfunction "C_3") (pintype "passive"))
      (node (ref "R11") (pin "1") (pinfunction "1_1") (pintype "passive"))
    )
    (net (code "40") (name "Net-(U1-V3)") (class "Default")
      (node (ref "C4") (pin "1") (pinfunction "1_1") (pintype "passive"))
      (node (ref "U1") (pin "5") (pinfunction "V3_5") (pintype "power_in"))
    )
    (net (code "41") (name "Net-(U1-XI)") (class "Default")
      (node (ref "C1") (pin "2") (pinfunction "2_2") (pintype "passive"))
      (node (ref "U1") (pin "9") (pinfunction "XI_9") (pintype "input"))
      (node (ref "Y1") (pin "2") (pinfunction "2_2") (pintype "passive"))
    )
    (net (code "42") (name "Net-(U1-XO)") (class "Default")
      (node (ref "C2") (pin "2") (pinfunction "2_2") (pintype "passive"))
      (node (ref "U1") (pin "10") (pinfunction "XO_10") (pintype "output"))
      (node (ref "Y1") (pin "1") (pinfunction "1_1") (pintype "passive"))
    )
    (net (code "43") (name "Net-(U2-CHRG)") (class "Default")
      (node (ref "D3") (pin "-") (pinfunction "-_-") (pintype "passive"))
      (node (ref "U2") (pin "7") (pinfunction "CHRG_7") (pintype "bidirectional"))
    )
    (net (code "44") (name "Net-(U2-DONE)") (class "Default")
      (node (ref "D4") (pin "-") (pinfunction "-_-") (pintype "passive"))
      (node (ref "U2") (pin "6") (pinfunction "DONE_6") (pintype "bidirectional"))
    )
    (net (code "45") (name "Net-(U2-ISET)") (class "Default")
      (node (ref "R1") (pin "2") (pinfunction "2_2") (pintype "passive"))
      (node (ref "U2") (pin "2") (pinfunction "ISET_2") (pintype "bidirectional"))
    )
    (net (code "46") (name "Net-(U3-FB)") (class "Default")
      (node (ref "R4") (pin "1") (pinfunction "1_1") (pintype "passive"))
      (node (ref "R5") (pin "2") (pinfunction "2_2") (pintype "passive"))
      (node (ref "U3") (pin "4") (pinfunction "FB_4") (pintype "bidirectional"))
    )
    (net (code "47") (name "Net-(U3-SW)") (class "Default")
      (node (ref "L1") (pin "1") (pinfunction "1_1") (pintype "passive"))
      (node (ref "U3") (pin "2") (pinfunction "SW_2") (pintype "bidirectional"))
    )
    (net (code "48") (name "RST") (class "Default")
      (node (ref "C15") (pin "2") (pinfunction "2_2") (pintype "passive"))
      (node (ref "J10") (pin "5") (pinfunction "5_5") (pintype "passive"))
      (node (ref "Q3") (pin "3") (pinfunction "C_3") (pintype "passive"))
      (node (ref "R13") (pin "2") (pinfunction "2_2") (pintype "passive"))
      (node (ref "R18") (pin "2") (pinfunction "2_2") (pintype "passive"))
      (node (ref "SW1") (pin "1") (pinfunction "1_1") (pintype "bidirectional"))
      (node (ref "U5") (pin "1") (pinfunction "RST_1") (pintype "bidirectional"))
    )
    (net (code "49") (name "RTS") (class "Default")
      (node (ref "Q3") (pin "2") (pinfunction "E_2") (pintype "passive"))
      (node (ref "R7") (pin "1") (pinfunction "1_1") (pintype "passive"))
      (node (ref "U1") (pin "16") (pinfunction "RTS#_16") (pintype "output"))
    )
    (net (code "50") (name "SCLK") (class "Default")
      (node (ref "J10") (pin "11") (pinfunction "11_11") (pintype "passive"))
      (node (ref "JP1") (pin "4") (pinfunction "4_4") (pintype "passive"))
      (node (ref "U5") (pin "14") (pinfunction "SCLK_14") (pintype "bidirectional"))
    )
    (net (code "51") (name "SOLUSB") (class "Default")
      (node (ref "C3") (pin "1") (pinfunction "1_1") (pintype "passive"))
      (node (ref "C5") (pin "+") (pinfunction "+_+") (pintype "passive"))
      (node (ref "C6") (pin "+") (pinfunction "+_+") (pintype "passive"))
      (node (ref "C8") (pin "2") (pinfunction "2_2") (pintype "passive"))
      (node (ref "D1") (pin "-") (pinfunction "-_-") (pintype "passive"))
      (node (ref "D2") (pin "-") (pinfunction "-_-") (pintype "passive"))
      (node (ref "Q1") (pin "C") (pinfunction "C_C") (pintype "bidirectional"))
      (node (ref "R3") (pin "2") (pinfunction "2_2") (pintype "passive"))
      (node (ref "U1") (pin "19") (pinfunction "VCC_19") (pintype "power_in"))
      (node (ref "U2") (pin "4") (pinfunction "VIN_4") (pintype "input"))
    )
    (net (code "52") (name "USB5V") (class "Default")
      (node (ref "D2") (pin "+") (pinfunction "+_+") (pintype "passive"))
      (node (ref "J1") (pin "1") (pinfunction "VCC_1") (pintype "bidirectional"))
    )
    (net (code "53") (name "VIN") (class "Default")
      (node (ref "J10") (pin "2") (pinfunction "2_2") (pintype "passive"))
      (node (ref "J7") (pin "1") (pinfunction "1_1") (pintype "bidirectional"))
    )
    (net (code "54") (name "unconnected-(J1-ID-Pad4)") (class "Default")
      (node (ref "J1") (pin "4") (pinfunction "ID_4") (pintype "bidirectional"))
    )
    (net (code "55") (name "unconnected-(U1-ACT#-Pad2)") (class "Default")
      (node (ref "U1") (pin "2") (pinfunction "ACT#_2") (pintype "output"))
    )
    (net (code "56") (name "unconnected-(U1-CKO-Pad1)") (class "Default")
      (node (ref "U1") (pin "1") (pinfunction "CKO_1") (pintype "output"))
    )
    (net (code "57") (name "unconnected-(U1-CTS#-Pad11)") (class "Default")
      (node (ref "U1") (pin "11") (pinfunction "CTS#_11") (pintype "input"))
    )
    (net (code "58") (name "unconnected-(U1-DCD#-Pad14)") (class "Default")
      (node (ref "U1") (pin "14") (pinfunction "DCD#_14") (pintype "input"))
    )
    (net (code "59") (name "unconnected-(U1-DSR#-Pad12)") (class "Default")
      (node (ref "U1") (pin "12") (pinfunction "DSR#_12") (pintype "input"))
    )
    (net (code "60") (name "unconnected-(U1-NC-Pad17)") (class "Default")
      (node (ref "U1") (pin "17") (pinfunction "NC_17") (pintype "no_connect"))
    )
    (net (code "61") (name "unconnected-(U1-R232-Pad18)") (class "Default")
      (node (ref "U1") (pin "18") (pinfunction "R232_18") (pintype "input"))
    )
    (net (code "62") (name "unconnected-(U1-RI#-Pad13)") (class "Default")
      (node (ref "U1") (pin "13") (pinfunction "RI#_13") (pintype "input"))
    )
    (net (code "63") (name "unconnected-(U4-NC-Pad3)") (class "Default")
      (node (ref "U4") (pin "3") (pinfunction "NC_3") (pintype "no_connect"))
    )
  )
)
